# Connectors.net
KiCad netlist of a schematic drawn in Altium Designer
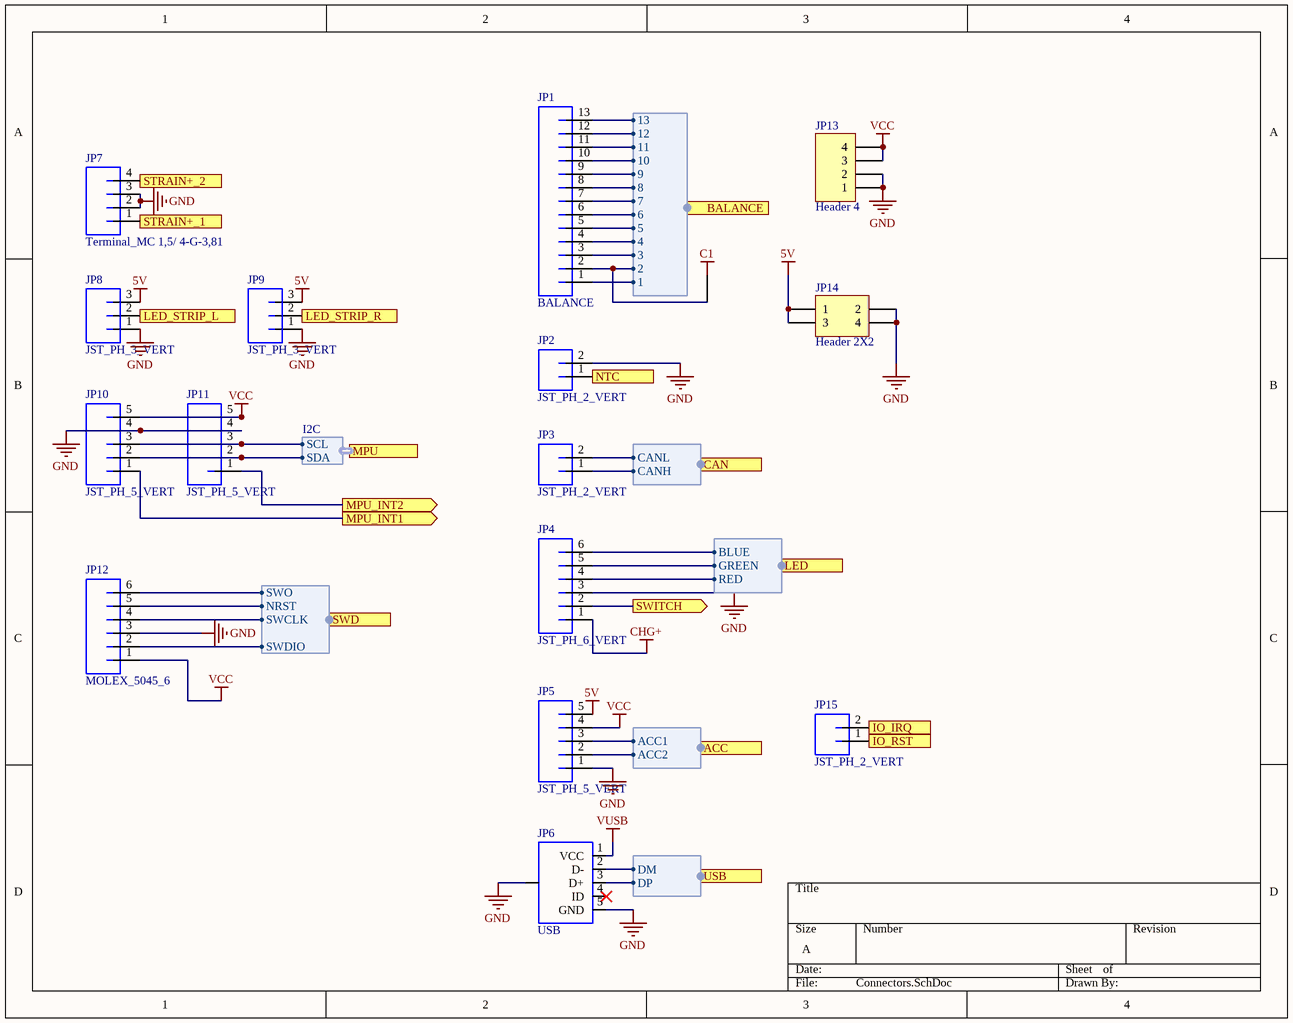
[diagram p0: Connectors.SchDoc]

(export (version "E")
  (design (tool "Eeschema 10.0.6"))
  (components
    (comp (ref "*1") (value "NetTie") (footprint "NetTie") (libsource (lib "Components") (part "NetTie")))
    (comp (ref "JP1")
      (value "BALANCE")
      (footprint "JST-XH-13-PTH-VERT")
      (fields
        (field (name "MANUFACTURER") "JST Sales America, Inc.")
        (field (name "PARTNUMBER") "B13B-XH-A(LF)(SN)")
      )
      (libsource (lib "Connectors-JST") (part "JST_XH_13_VERT"))
    )
    (comp (ref "JP2")
      (value "JST_PH_2_VERT")
      (footprint "JST-PH-2-PTH-VERT")
      (fields
        (field (name "MANUFACTURER") "JST Sales America Inc.")
        (field (name "PARTNUMBER") "B2B-PH-K-S(LF)(SN)")
      )
      (libsource (lib "Connectors") (part "JST_PH_2_VERT"))
    )
    (comp (ref "JP3")
      (value "JST_PH_2_VERT")
      (footprint "JST-PH-2-PTH-VERT")
      (fields
        (field (name "MANUFACTURER") "JST Sales America Inc.")
        (field (name "PARTNUMBER") "B2B-PH-K-S(LF)(SN)")
      )
      (libsource (lib "Connectors") (part "JST_PH_2_VERT"))
    )
    (comp (ref "JP4")
      (value "JST_PH_6_VERT")
      (footprint "JST-PH-6-PTH-VERT")
      (fields
        (field (name "PARTNUMBER") "B6B-PH-K-S(LF)(SN)")
        (field (name "MANUFACTURER") "JST Sales America Inc.")
      )
      (libsource (lib "Connectors") (part "JST_PH_6_VERT"))
    )
    (comp (ref "JP5")
      (value "JST_PH_5_VERT")
      (footprint "JST-PH-5-PTH-VERT")
      (fields
        (field (name "MANUFACTURER") "JST Sales America, Inc.")
        (field (name "PARTNUMBER") "B5B-PH-K-S(LF)(SN)")
      )
      (libsource (lib "Connectors") (part "JST_PH_5_VERT"))
    )
    (comp (ref "JP6")
      (value "USB")
      (footprint "USB-MICROB_HORZ")
      (fields (field (name "PARTNUMBER") "10118192-0001LF") (field (name "MANUFACTURER") "Amphenol FCI"))
      (libsource (lib "Connectors") (part "USB_MICROB_SMT"))
    )
    (comp (ref "JP7")
      (value "Terminal_MC 1,5/ 4-G-3,81")
      (footprint "Terminal-3.81-HORZ")
      (fields
        (field (name "PARTNUMBER") "1803293")
        (field (name "MANUFACTURER") "Phoenix Contact")
        (field (name "MATEPART") "1803594")
      )
      (libsource (lib "Connectors") (part "Terminal_MC 1,5/ 4-G-3,81"))
    )
    (comp (ref "JP8")
      (value "JST_PH_3_VERT")
      (footprint "JST-PH-3-PTH-VERT")
      (fields
        (field (name "MANUFACTURER") "JST Sales America Inc.")
        (field (name "PARTNUMBER") "B3B-PH-K-S(LF)(SN)")
      )
      (libsource (lib "Connectors") (part "JST_PH_3_VERT"))
    )
    (comp (ref "JP9")
      (value "JST_PH_3_VERT")
      (footprint "JST-PH-3-PTH-VERT")
      (fields
        (field (name "MANUFACTURER") "JST Sales America Inc.")
        (field (name "PARTNUMBER") "B3B-PH-K-S(LF)(SN)")
      )
      (libsource (lib "Connectors") (part "JST_PH_3_VERT"))
    )
    (comp (ref "JP10")
      (value "JST_PH_5_VERT")
      (footprint "JST-PH-5-PTH-VERT")
      (fields
        (field (name "MANUFACTURER") "JST Sales America, Inc.")
        (field (name "PARTNUMBER") "B5B-PH-K-S(LF)(SN)")
      )
      (libsource (lib "Connectors") (part "JST_PH_5_VERT"))
    )
    (comp (ref "JP11")
      (value "JST_PH_5_VERT")
      (footprint "JST-PH-5-PTH-VERT")
      (fields
        (field (name "MANUFACTURER") "JST Sales America, Inc.")
        (field (name "PARTNUMBER") "B5B-PH-K-S(LF)(SN)")
      )
      (libsource (lib "Connectors") (part "JST_PH_5_VERT"))
    )
    (comp (ref "JP12")
      (value "MOLEX_5045_6")
      (footprint "MOLEX_5045_6")
      (fields
        (field (name "PARTNUMBER") "B6B-PH-K-S(LF)(SN)")
        (field (name "MANUFACTURER") "JST Sales America Inc.")
      )
      (libsource (lib "Connectors") (part "MOLEX_5045_6"))
    )
    (comp (ref "JP13")
      (value "Header 4")
      (footprint "HDR1X4")
      (description "Header, 4-Pin")
      (fields (field (name "PUBLISHER") "Altium Limited"))
      (libsource (lib "Miscellaneous Connectors") (part "Header 4"))
    )
    (comp (ref "JP14")
      (value "Header 2X2")
      (footprint "HDR2X2")
      (description "Header, 2-Pin, Dual row")
      (fields (field (name "PUBLISHER") "Altium Limited"))
      (libsource (lib "Miscellaneous Connectors") (part "Header 2X2"))
    )
    (comp (ref "JP15")
      (value "JST_PH_2_VERT")
      (footprint "JST-PH-2-PTH-VERT")
      (fields
        (field (name "MANUFACTURER") "JST Sales America Inc.")
        (field (name "PARTNUMBER") "B2B-PH-K-S(LF)(SN)")
      )
      (libsource (lib "Connectors") (part "JST_PH_2_VERT"))
    )
  )
  (nets
    (net (code "10") (name "/1") (class "Default")
      (node (ref "JP1") (pin "1") (pinfunction "1_1") (pintype "passive"))
    )
    (net (code "11") (name "/2") (class "Default")
      (node (ref "*1") (pin "1") (pinfunction "1_1") (pintype "passive"))
      (node (ref "JP1") (pin "2") (pinfunction "2_2") (pintype "passive"))
    )
    (net (code "12") (name "/3") (class "Default")
      (node (ref "JP1") (pin "3") (pinfunction "3_3") (pintype "passive"))
    )
    (net (code "13") (name "/4") (class "Default")
      (node (ref "JP1") (pin "4") (pinfunction "4_4") (pintype "passive"))
    )
    (net (code "14") (name "/5") (class "Default")
      (node (ref "JP1") (pin "5") (pinfunction "5_5") (pintype "passive"))
    )
    (net (code "15") (name "/6") (class "Default")
      (node (ref "JP1") (pin "6") (pinfunction "6_6") (pintype "passive"))
    )
    (net (code "16") (name "/7") (class "Default")
      (node (ref "JP1") (pin "7") (pinfunction "7_7") (pintype "passive"))
    )
    (net (code "17") (name "/8") (class "Default")
      (node (ref "JP1") (pin "8") (pinfunction "8_8") (pintype "passive"))
    )
    (net (code "18") (name "/9") (class "Default")
      (node (ref "JP1") (pin "9") (pinfunction "9_9") (pintype "passive"))
    )
    (net (code "19") (name "/10") (class "Default")
      (node (ref "JP1") (pin "10") (pinfunction "10_10") (pintype "passive"))
    )
    (net (code "20") (name "/11") (class "Default")
      (node (ref "JP1") (pin "11") (pinfunction "11_11") (pintype "passive"))
    )
    (net (code "21") (name "/12") (class "Default")
      (node (ref "JP1") (pin "12") (pinfunction "12_12") (pintype "passive"))
    )
    (net (code "22") (name "/13") (class "Default")
      (node (ref "JP1") (pin "13") (pinfunction "13_13") (pintype "passive"))
    )
    (net (code "23") (name "/ACC1") (class "Default")
      (node (ref "JP5") (pin "3") (pinfunction "3_3") (pintype "passive"))
    )
    (net (code "24") (name "/ACC2") (class "Default")
      (node (ref "JP5") (pin "2") (pinfunction "2_2") (pintype "passive"))
    )
    (net (code "25") (name "/BLUE") (class "Default")
      (node (ref "JP4") (pin "6") (pinfunction "6_6") (pintype "passive"))
    )
    (net (code "26") (name "/CANH") (class "Default")
      (node (ref "JP3") (pin "1") (pinfunction "1_1") (pintype "passive"))
    )
    (net (code "27") (name "/CANL") (class "Default")
      (node (ref "JP3") (pin "2") (pinfunction "2_2") (pintype "passive"))
    )
    (net (code "28") (name "/DM") (class "Default")
      (node (ref "JP6") (pin "2") (pinfunction "D-_2") (pintype "passive"))
    )
    (net (code "29") (name "/DP") (class "Default")
      (node (ref "JP6") (pin "3") (pinfunction "D+_3") (pintype "passive"))
    )
    (net (code "30") (name "/GREEN") (class "Default")
      (node (ref "JP4") (pin "5") (pinfunction "5_5") (pintype "passive"))
    )
    (net (code "31") (name "/IO_IRQ") (class "Default")
      (node (ref "JP15") (pin "2") (pinfunction "2_2") (pintype "passive"))
    )
    (net (code "32") (name "/IO_RST") (class "Default")
      (node (ref "JP15") (pin "1") (pinfunction "1_1") (pintype "passive"))
    )
    (net (code "33") (name "/LED_STRIP_L") (class "Default")
      (node (ref "JP8") (pin "2") (pinfunction "2_2") (pintype "passive"))
    )
    (net (code "34") (name "/LED_STRIP_R") (class "Default")
      (node (ref "JP9") (pin "2") (pinfunction "2_2") (pintype "passive"))
    )
    (net (code "35") (name "/MPU_INT1") (class "Default")
      (node (ref "JP10") (pin "1") (pinfunction "1_1") (pintype "passive"))
    )
    (net (code "36") (name "/MPU_INT2") (class "Default")
      (node (ref "JP11") (pin "1") (pinfunction "1_1") (pintype "passive"))
    )
    (net (code "37") (name "/NRST") (class "Default")
      (node (ref "JP12") (pin "5") (pinfunction "5_5") (pintype "passive"))
    )
    (net (code "38") (name "/NTC") (class "Default")
      (node (ref "JP2") (pin "1") (pinfunction "1_1") (pintype "passive"))
    )
    (net (code "39") (name "/RED") (class "Default")
      (node (ref "JP4") (pin "4") (pinfunction "4_4") (pintype "passive"))
    )
    (net (code "40") (name "/SCL") (class "Default")
      (node (ref "JP10") (pin "3") (pinfunction "3_3") (pintype "passive"))
      (node (ref "JP11") (pin "3") (pinfunction "3_3") (pintype "passive"))
    )
    (net (code "41") (name "/SDA") (class "Default")
      (node (ref "JP10") (pin "2") (pinfunction "2_2") (pintype "passive"))
      (node (ref "JP11") (pin "2") (pinfunction "2_2") (pintype "passive"))
    )
    (net (code "42") (name "/STRAIN+_1") (class "Default")
      (node (ref "JP7") (pin "1") (pinfunction "1_1") (pintype "passive"))
    )
    (net (code "43") (name "/STRAIN+_2") (class "Default")
      (node (ref "JP7") (pin "4") (pinfunction "4_4") (pintype "passive"))
    )
    (net (code "44") (name "/SWCLK") (class "Default")
      (node (ref "JP12") (pin "4") (pinfunction "4_4") (pintype "passive"))
    )
    (net (code "45") (name "/SWDIO") (class "Default")
      (node (ref "JP12") (pin "2") (pinfunction "2_2") (pintype "passive"))
    )
    (net (code "46") (name "/SWITCH") (class "Default")
      (node (ref "JP4") (pin "2") (pinfunction "2_2") (pintype "passive"))
    )
    (net (code "47") (name "/SWO") (class "Default")
      (node (ref "JP12") (pin "6") (pinfunction "6_6") (pintype "passive"))
    )
    (net (code "55") (name "5V") (class "Default")
      (node (ref "JP14") (pin "1") (pinfunction "1_1") (pintype "passive"))
      (node (ref "JP14") (pin "3") (pinfunction "3_3") (pintype "passive"))
      (node (ref "JP5") (pin "5") (pinfunction "5_5") (pintype "passive"))
      (node (ref "JP8") (pin "3") (pinfunction "3_3") (pintype "passive"))
      (node (ref "JP9") (pin "3") (pinfunction "3_3") (pintype "passive"))
    )
    (net (code "56") (name "C1") (class "Default")
      (node (ref "*1") (pin "2") (pinfunction "2_2") (pintype "passive"))
    )
    (net (code "57") (name "CHG+") (class "Default")
      (node (ref "JP4") (pin "1") (pinfunction "1_1") (pintype "passive"))
    )
    (net (code "58") (name "GND") (class "Default")
      (node (ref "JP10") (pin "4") (pinfunction "4_4") (pintype "passive"))
      (node (ref "JP11") (pin "4") (pinfunction "4_4") (pintype "passive"))
      (node (ref "JP12") (pin "3") (pinfunction "3_3") (pintype "passive"))
      (node (ref "JP13") (pin "1") (pinfunction "1_1") (pintype "passive"))
      (node (ref "JP13") (pin "2") (pinfunction "2_2") (pintype "passive"))
      (node (ref "JP14") (pin "2") (pinfunction "2_2") (pintype "passive"))
      (node (ref "JP14") (pin "4") (pinfunction "4_4") (pintype "passive"))
      (node (ref "JP2") (pin "2") (pinfunction "2_2") (pintype "passive"))
      (node (ref "JP4") (pin "3") (pinfunction "3_3") (pintype "passive"))
      (node (ref "JP5") (pin "1") (pinfunction "1_1") (pintype "passive"))
      (node (ref "JP6") (pin "5") (pinfunction "GND_5") (pintype "passive"))
      (node (ref "JP6") (pin "6") (pinfunction "SHIELD_6") (pintype "passive"))
      (node (ref "JP7") (pin "2") (pinfunction "2_2") (pintype "passive"))
      (node (ref "JP7") (pin "3") (pinfunction "3_3") (pintype "passive"))
      (node (ref "JP8") (pin "1") (pinfunction "1_1") (pintype "passive"))
      (node (ref "JP9") (pin "1") (pinfunction "1_1") (pintype "passive"))
    )
    (net (code "59") (name "VCC") (class "Default")
      (node (ref "JP10") (pin "5") (pinfunction "5_5") (pintype "passive"))
      (node (ref "JP11") (pin "5") (pinfunction "5_5") (pintype "passive"))
      (node (ref "JP12") (pin "1") (pinfunction "1_1") (pintype "passive"))
      (node (ref "JP13") (pin "3") (pinfunction "3_3") (pintype "passive"))
      (node (ref "JP13") (pin "4") (pinfunction "4_4") (pintype "passive"))
      (node (ref "JP5") (pin "4") (pinfunction "4_4") (pintype "passive"))
    )
    (net (code "60") (name "VUSB") (class "Default")
      (node (ref "JP6") (pin "1") (pinfunction "VCC_1") (pintype "passive"))
    )
    (net (code "61") (name "unconnected-(JP6-ID-Pad4)") (class "Default")
      (node (ref "JP6") (pin "4") (pinfunction "ID_4") (pintype "passive+no_connect"))
    )
  )
)
